# MCP1603-breakout.net
KiCad netlist of a schematic drawn in EAGLE
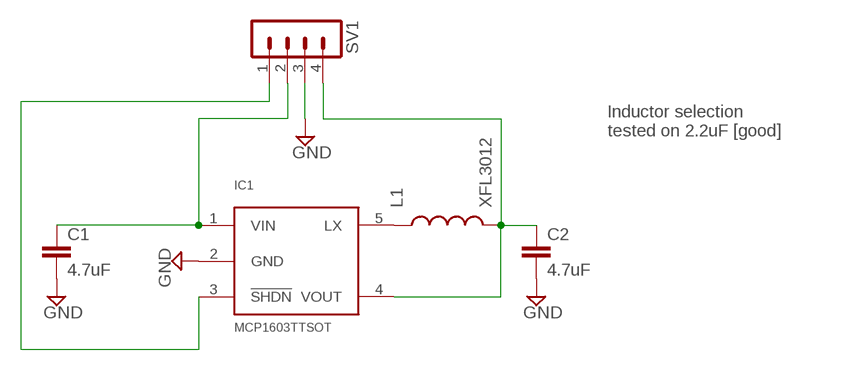
[diagram p0: schematic, sheet 1]

(export (version "E")
  (design (tool "Eeschema 10.0.6"))
  (components
    (comp (ref "C1")
      (value "4.7uF")
      (footprint "eagle-import:C0603")
      (libsource (lib "eagle-import") (part "C-EUC0603"))
    )
    (comp (ref "C2")
      (value "4.7uF")
      (footprint "eagle-import:C0603")
      (libsource (lib "eagle-import") (part "C-EUC0603"))
    )
    (comp (ref "IC1")
      (value "MCP1603TTSOT")
      (footprint "eagle-import:TSOT23-6")
      (libsource (lib "eagle-import") (part "MCP1603TTSOT"))
    )
    (comp (ref "L1")
      (value "XFL3012")
      (footprint "eagle-import:XFL3012")
      (libsource (lib "eagle-import") (part "XFL3012"))
    )
    (comp (ref "SV1")
      (value "MA04-1")
      (footprint "eagle-import:MA04-1")
      (libsource (lib "eagle-import") (part "MA04-1"))
    )
  )
  (nets
    (net (code "1") (name "GND") (class "Default")
      (node (ref "C1") (pin "2") (pinfunction "2_2") (pintype "passive"))
      (node (ref "C2") (pin "2") (pinfunction "2_2") (pintype "passive"))
      (node (ref "IC1") (pin "2") (pinfunction "GND_2") (pintype "power_in"))
      (node (ref "SV1") (pin "3") (pinfunction "3_3") (pintype "passive"))
    )
    (net (code "2") (name "Net-(IC1-LX)") (class "Default")
      (node (ref "IC1") (pin "5") (pinfunction "LX_5") (pintype "bidirectional"))
      (node (ref "L1") (pin "1") (pinfunction "1_1") (pintype "passive"))
    )
    (net (code "3") (name "Net-(IC1-VIN)") (class "Default")
      (node (ref "C1") (pin "1") (pinfunction "1_1") (pintype "passive"))
      (node (ref "IC1") (pin "1") (pinfunction "VIN_1") (pintype "power_in"))
      (node (ref "SV1") (pin "2") (pinfunction "2_2") (pintype "passive"))
    )
    (net (code "4") (name "Net-(IC1-VOUT)") (class "Default")
      (node (ref "C2") (pin "1") (pinfunction "1_1") (pintype "passive"))
      (node (ref "IC1") (pin "4") (pinfunction "VOUT_4") (pintype "power_in"))
      (node (ref "L1") (pin "2") (pinfunction "2_2") (pintype "passive"))
      (node (ref "SV1") (pin "4") (pinfunction "4_4") (pintype "passive"))
    )
    (net (code "5") (name "Net-(IC1-~{SHDN})") (class "Default")
      (node (ref "IC1") (pin "3") (pinfunction "~{SHDN}_3") (pintype "bidirectional"))
      (node (ref "SV1") (pin "1") (pinfunction "1_1") (pintype "passive"))
    )
  )
)
